# ATmegaBootloader.net
KiCad netlist of a schematic drawn in EAGLE
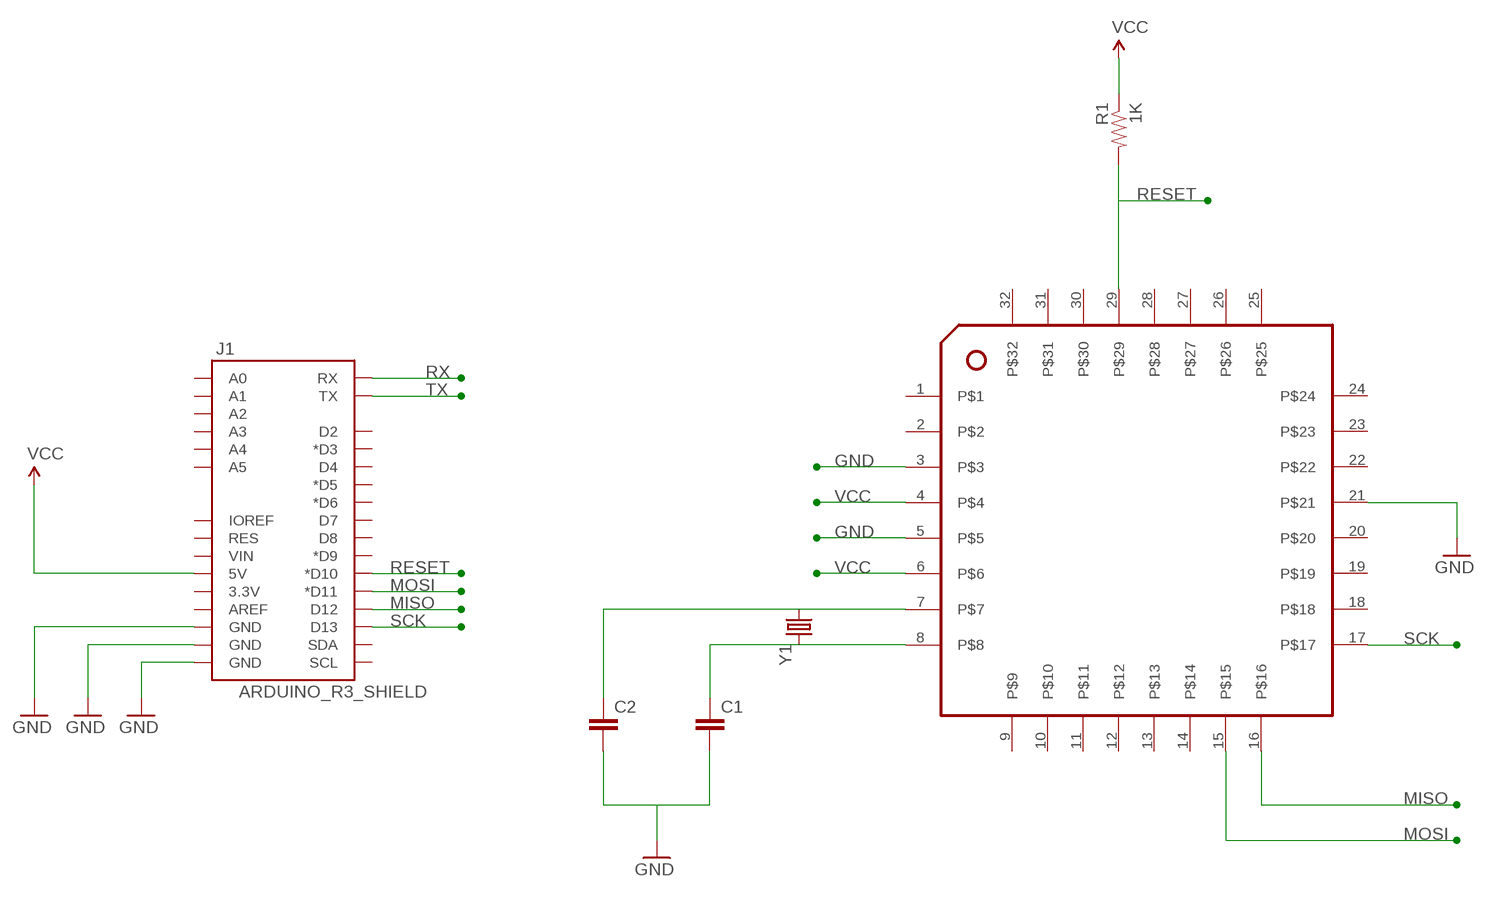
[diagram p0: schematic, sheet 1]

(export (version "E")
  (design (tool "Eeschema 10.0.6"))
  (components
    (comp (ref "C1")
      (value "0.1UF-50V-20%(PTH)KIT-EZ")
      (footprint "eagle-import:CAP-PTH-SMALL-KIT")
      (libsource (lib "eagle-import") (part "0.1UF-50V-20%(PTH)KIT-EZ"))
    )
    (comp (ref "C2")
      (value "0.1UF-50V-20%(PTH)KIT-EZ")
      (footprint "eagle-import:CAP-PTH-SMALL-KIT")
      (libsource (lib "eagle-import") (part "0.1UF-50V-20%(PTH)KIT-EZ"))
    )
    (comp (ref "J1")
      (value "ARDUINO_R3_SHIELD")
      (footprint "eagle-import:UNO_R3_SHIELD")
      (libsource (lib "eagle-import") (part "ARDUINO_R3_SHIELD"))
    )
    (comp (ref "R1")
      (value "1K")
      (footprint "eagle-import:AXIAL-0.3")
      (libsource (lib "eagle-import") (part "1KOHM-1/4W-1%(PTH)"))
    )
    (comp (ref "U$1")
      (value "ATMEGA-TQFP-BREAKOUT")
      (footprint "eagle-import:TQFP32-BREAKOUT")
      (libsource (lib "eagle-import") (part "ATMEGA-TQFP-BREAKOUT"))
    )
    (comp (ref "Y1")
      (value "CRYSTALHC49US")
      (footprint "eagle-import:HC49US")
      (libsource (lib "eagle-import") (part "CRYSTALHC49US"))
    )
  )
  (nets
    (net (code "1") (name "/MISO") (class "Default")
      (node (ref "J1") (pin "D12") (pinfunction "D12_D12") (pintype "bidirectional"))
      (node (ref "U$1") (pin "16") (pinfunction "P$16_16") (pintype "bidirectional"))
    )
    (net (code "2") (name "/MOSI") (class "Default")
      (node (ref "J1") (pin "D11") (pinfunction "*D11_D11") (pintype "bidirectional"))
      (node (ref "U$1") (pin "15") (pinfunction "P$15_15") (pintype "bidirectional"))
    )
    (net (code "3") (name "/RESET") (class "Default")
      (node (ref "J1") (pin "D10") (pinfunction "*D10_D10") (pintype "bidirectional"))
      (node (ref "R1") (pin "P$2") (pinfunction "2_P$2") (pintype "passive"))
      (node (ref "U$1") (pin "29") (pinfunction "P$29_29") (pintype "bidirectional"))
    )
    (net (code "4") (name "/RX") (class "Default")
      (node (ref "J1") (pin "RX") (pinfunction "RX_RX") (pintype "bidirectional"))
    )
    (net (code "5") (name "/SCK") (class "Default")
      (node (ref "J1") (pin "D13") (pinfunction "D13_D13") (pintype "bidirectional"))
      (node (ref "U$1") (pin "17") (pinfunction "P$17_17") (pintype "bidirectional"))
    )
    (net (code "6") (name "/TX") (class "Default")
      (node (ref "J1") (pin "TX") (pinfunction "TX_TX") (pintype "bidirectional"))
    )
    (net (code "7") (name "GND") (class "Default")
      (node (ref "C1") (pin "2") (pinfunction "2_2") (pintype "passive"))
      (node (ref "C2") (pin "2") (pinfunction "2_2") (pintype "passive"))
      (node (ref "J1") (pin "GND@0") (pinfunction "GND_GND@0") (pintype "bidirectional"))
      (node (ref "J1") (pin "GND@1") (pinfunction "GND_GND@1") (pintype "bidirectional"))
      (node (ref "J1") (pin "GND@2") (pinfunction "GND_GND@2") (pintype "bidirectional"))
      (node (ref "U$1") (pin "21") (pinfunction "P$21_21") (pintype "bidirectional"))
      (node (ref "U$1") (pin "3") (pinfunction "P$3_3") (pintype "bidirectional"))
      (node (ref "U$1") (pin "5") (pinfunction "P$5_5") (pintype "bidirectional"))
    )
    (net (code "8") (name "Net-(U$1-P$7)") (class "Default")
      (node (ref "C2") (pin "1") (pinfunction "1_1") (pintype "passive"))
      (node (ref "U$1") (pin "7") (pinfunction "P$7_7") (pintype "bidirectional"))
      (node (ref "Y1") (pin "1") (pinfunction "1_1") (pintype "passive"))
    )
    (net (code "9") (name "Net-(U$1-P$8)") (class "Default")
      (node (ref "C1") (pin "1") (pinfunction "1_1") (pintype "passive"))
      (node (ref "U$1") (pin "8") (pinfunction "P$8_8") (pintype "bidirectional"))
      (node (ref "Y1") (pin "2") (pinfunction "2_2") (pintype "passive"))
    )
    (net (code "10") (name "VCC") (class "Default")
      (node (ref "J1") (pin "5V") (pinfunction "5V_5V") (pintype "bidirectional"))
      (node (ref "R1") (pin "P$1") (pinfunction "1_P$1") (pintype "passive"))
      (node (ref "U$1") (pin "4") (pinfunction "P$4_4") (pintype "bidirectional"))
      (node (ref "U$1") (pin "6") (pinfunction "P$6_6") (pintype "bidirectional"))
    )
    (net (code "11") (name "unconnected-(J1-*D3-PadD3)") (class "Default")
      (node (ref "J1") (pin "D3") (pinfunction "*D3_D3") (pintype "bidirectional"))
    )
    (net (code "12") (name "unconnected-(J1-*D5-PadD5)") (class "Default")
      (node (ref "J1") (pin "D5") (pinfunction "*D5_D5") (pintype "bidirectional"))
    )
    (net (code "13") (name "unconnected-(J1-*D6-PadD6)") (class "Default")
      (node (ref "J1") (pin "D6") (pinfunction "*D6_D6") (pintype "bidirectional"))
    )
    (net (code "14") (name "unconnected-(J1-*D9-PadD9)") (class "Default")
      (node (ref "J1") (pin "D9") (pinfunction "*D9_D9") (pintype "bidirectional"))
    )
    (net (code "15") (name "unconnected-(J1-Pad3.3V)") (class "Default")
      (node (ref "J1") (pin "3.3V") (pinfunction "3.3V_3.3V") (pintype "bidirectional"))
    )
    (net (code "16") (name "unconnected-(J1-PadA0)") (class "Default")
      (node (ref "J1") (pin "A0") (pinfunction "A0_A0") (pintype "bidirectional"))
    )
    (net (code "17") (name "unconnected-(J1-PadA1)") (class "Default")
      (node (ref "J1") (pin "A1") (pinfunction "A1_A1") (pintype "bidirectional"))
    )
    (net (code "18") (name "unconnected-(J1-PadA2)") (class "Default")
      (node (ref "J1") (pin "A2") (pinfunction "A2_A2") (pintype "bidirectional"))
    )
    (net (code "19") (name "unconnected-(J1-PadA3)") (class "Default")
      (node (ref "J1") (pin "A3") (pinfunction "A3_A3") (pintype "bidirectional"))
    )
    (net (code "20") (name "unconnected-(J1-PadA4)") (class "Default")
      (node (ref "J1") (pin "A4") (pinfunction "A4_A4") (pintype "bidirectional"))
    )
    (net (code "21") (name "unconnected-(J1-PadA5)") (class "Default")
      (node (ref "J1") (pin "A5") (pinfunction "A5_A5") (pintype "bidirectional"))
    )
    (net (code "22") (name "unconnected-(J1-PadAREF)") (class "Default")
      (node (ref "J1") (pin "AREF") (pinfunction "AREF_AREF") (pintype "bidirectional"))
    )
    (net (code "23") (name "unconnected-(J1-PadD2)") (class "Default")
      (node (ref "J1") (pin "D2") (pinfunction "D2_D2") (pintype "bidirectional"))
    )
    (net (code "24") (name "unconnected-(J1-PadD4)") (class "Default")
      (node (ref "J1") (pin "D4") (pinfunction "D4_D4") (pintype "bidirectional"))
    )
    (net (code "25") (name "unconnected-(J1-PadD7)") (class "Default")
      (node (ref "J1") (pin "D7") (pinfunction "D7_D7") (pintype "bidirectional"))
    )
    (net (code "26") (name "unconnected-(J1-PadD8)") (class "Default")
      (node (ref "J1") (pin "D8") (pinfunction "D8_D8") (pintype "bidirectional"))
    )
    (net (code "27") (name "unconnected-(J1-PadIOREF)") (class "Default")
      (node (ref "J1") (pin "IOREF") (pinfunction "IOREF_IOREF") (pintype "bidirectional"))
    )
    (net (code "28") (name "unconnected-(J1-PadRES)") (class "Default")
      (node (ref "J1") (pin "RES") (pinfunction "RES_RES") (pintype "bidirectional"))
    )
    (net (code "29") (name "unconnected-(J1-PadSCL)") (class "Default")
      (node (ref "J1") (pin "SCL") (pinfunction "SCL_SCL") (pintype "bidirectional"))
    )
    (net (code "30") (name "unconnected-(J1-PadSDA)") (class "Default")
      (node (ref "J1") (pin "SDA") (pinfunction "SDA_SDA") (pintype "bidirectional"))
    )
    (net (code "31") (name "unconnected-(J1-PadVIN)") (class "Default")
      (node (ref "J1") (pin "VIN") (pinfunction "VIN_VIN") (pintype "bidirectional"))
    )
    (net (code "32") (name "unconnected-(U$1-P$1-Pad1)") (class "Default")
      (node (ref "U$1") (pin "1") (pinfunction "P$1_1") (pintype "bidirectional"))
    )
    (net (code "33") (name "unconnected-(U$1-P$2-Pad2)") (class "Default")
      (node (ref "U$1") (pin "2") (pinfunction "P$2_2") (pintype "bidirectional"))
    )
    (net (code "34") (name "unconnected-(U$1-P$9-Pad9)") (class "Default")
      (node (ref "U$1") (pin "9") (pinfunction "P$9_9") (pintype "bidirectional"))
    )
    (net (code "35") (name "unconnected-(U$1-P$10-Pad10)") (class "Default")
      (node (ref "U$1") (pin "10") (pinfunction "P$10_10") (pintype "bidirectional"))
    )
    (net (code "36") (name "unconnected-(U$1-P$11-Pad11)") (class "Default")
      (node (ref "U$1") (pin "11") (pinfunction "P$11_11") (pintype "bidirectional"))
    )
    (net (code "37") (name "unconnected-(U$1-P$12-Pad12)") (class "Default")
      (node (ref "U$1") (pin "12") (pinfunction "P$12_12") (pintype "bidirectional"))
    )
    (net (code "38") (name "unconnected-(U$1-P$13-Pad13)") (class "Default")
      (node (ref "U$1") (pin "13") (pinfunction "P$13_13") (pintype "bidirectional"))
    )
    (net (code "39") (name "unconnected-(U$1-P$14-Pad14)") (class "Default")
      (node (ref "U$1") (pin "14") (pinfunction "P$14_14") (pintype "bidirectional"))
    )
    (net (code "40") (name "unconnected-(U$1-P$18-Pad18)") (class "Default")
      (node (ref "U$1") (pin "18") (pinfunction "P$18_18") (pintype "bidirectional"))
    )
    (net (code "41") (name "unconnected-(U$1-P$19-Pad19)") (class "Default")
      (node (ref "U$1") (pin "19") (pinfunction "P$19_19") (pintype "bidirectional"))
    )
    (net (code "42") (name "unconnected-(U$1-P$20-Pad20)") (class "Default")
      (node (ref "U$1") (pin "20") (pinfunction "P$20_20") (pintype "bidirectional"))
    )
    (net (code "43") (name "unconnected-(U$1-P$22-Pad22)") (class "Default")
      (node (ref "U$1") (pin "22") (pinfunction "P$22_22") (pintype "bidirectional"))
    )
    (net (code "44") (name "unconnected-(U$1-P$23-Pad23)") (class "Default")
      (node (ref "U$1") (pin "23") (pinfunction "P$23_23") (pintype "bidirectional"))
    )
    (net (code "45") (name "unconnected-(U$1-P$24-Pad24)") (class "Default")
      (node (ref "U$1") (pin "24") (pinfunction "P$24_24") (pintype "bidirectional"))
    )
    (net (code "46") (name "unconnected-(U$1-P$25-Pad25)") (class "Default")
      (node (ref "U$1") (pin "25") (pinfunction "P$25_25") (pintype "bidirectional"))
    )
    (net (code "47") (name "unconnected-(U$1-P$26-Pad26)") (class "Default")
      (node (ref "U$1") (pin "26") (pinfunction "P$26_26") (pintype "bidirectional"))
    )
    (net (code "48") (name "unconnected-(U$1-P$27-Pad27)") (class "Default")
      (node (ref "U$1") (pin "27") (pinfunction "P$27_27") (pintype "bidirectional"))
    )
    (net (code "49") (name "unconnected-(U$1-P$28-Pad28)") (class "Default")
      (node (ref "U$1") (pin "28") (pinfunction "P$28_28") (pintype "bidirectional"))
    )
    (net (code "50") (name "unconnected-(U$1-P$30-Pad30)") (class "Default")
      (node (ref "U$1") (pin "30") (pinfunction "P$30_30") (pintype "bidirectional"))
    )
    (net (code "51") (name "unconnected-(U$1-P$31-Pad31)") (class "Default")
      (node (ref "U$1") (pin "31") (pinfunction "P$31_31") (pintype "bidirectional"))
    )
    (net (code "52") (name "unconnected-(U$1-P$32-Pad32)") (class "Default")
      (node (ref "U$1") (pin "32") (pinfunction "P$32_32") (pintype "bidirectional"))
    )
  )
)
